# electro3_sensor.net
KiCad netlist of a schematic drawn in Altium Designer
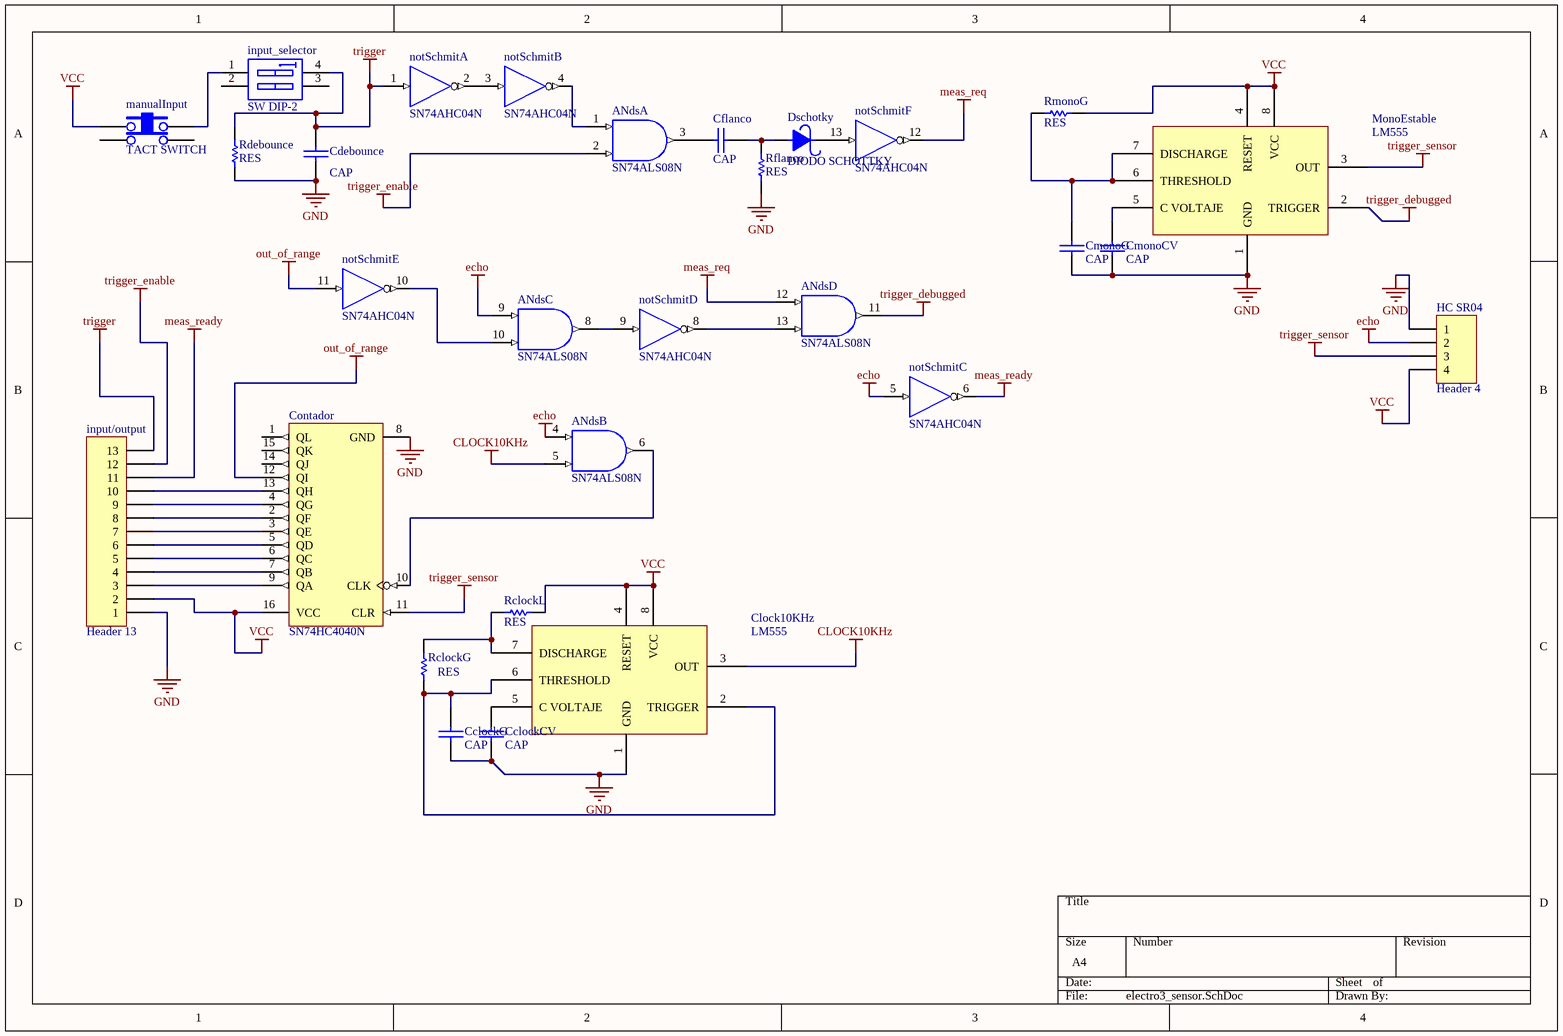
[diagram p0: electro3_sensor.SchDoc]

(export (version "E")
  (design (tool "Eeschema 10.0.6"))
  (components
    (comp (ref "ANds")
      (value "SN74ALS08N")
      (footprint "N014")
      (description "Quadruple 2-Input Positive-AND Gate")
      (fields (field (name "PUBLISHER") "Altium Limited"))
      (libsource (lib "TI Logic Gate 1") (part "SN74ALS08N"))
    )
    (comp (ref "CclockCV") (value "CAP") (footprint "CAP200") (libsource (lib "LIBEBAL") (part "CAP")))
    (comp (ref "CclockG") (value "CAP") (footprint "CAP200") (libsource (lib "LIBEBAL") (part "CAP")))
    (comp (ref "Cdebounce") (value "CAP") (footprint "CAP200") (libsource (lib "LIBEBAL") (part "CAP")))
    (comp (ref "Cflanco") (value "CAP") (footprint "CAP200") (libsource (lib "LIBEBAL") (part "CAP")))
    (comp (ref "Clock10KHz")
      (value "LM555")
      (footprint "DIP8")
      (description "Timer")
      (libsource (lib "LIBEBAL") (part "LM555"))
    )
    (comp (ref "CmonoCV") (value "CAP") (footprint "CAP200") (libsource (lib "LIBEBAL") (part "CAP")))
    (comp (ref "CmonoG") (value "CAP") (footprint "CAP200") (libsource (lib "LIBEBAL") (part "CAP")))
    (comp (ref "Contador")
      (value "SN74HC4040N")
      (footprint "N016")
      (description "12-Bit Asynchronous Binary Counter")
      (fields (field (name "PUBLISHER") "Altium Limited"))
      (libsource (lib "TI Logic Counter") (part "SN74HC4040N"))
    )
    (comp (ref "Dschotky")
      (value "DIODO SCHOTTKY")
      (footprint "DO41")
      (libsource (lib "LIBEBAL") (part "DIODO SCHOTTKY"))
    )
    (comp (ref "HC SR04")
      (value "Header 4")
      (footprint "HDR1X4")
      (description "Header, 4-Pin")
      (fields (field (name "PUBLISHER") "Altium Limited"))
      (libsource (lib "Miscellaneous Connectors") (part "Header 4"))
    )
    (comp (ref "input/output")
      (value "Header 13")
      (footprint "HDR1X13")
      (description "Header, 13-Pin")
      (fields (field (name "PUBLISHER") "Altium Limited"))
      (libsource (lib "Miscellaneous Connectors") (part "Header 13"))
    )
    (comp (ref "input_selector")
      (value "SW DIP-2")
      (footprint "DIP-4")
      (description "DIP Switch, 2 Position, SPST")
      (fields (field (name "PUBLISHER") "Altium Limited"))
      (libsource (lib "Miscellaneous Devices") (part "SW DIP-2"))
    )
    (comp (ref "manualInput")
      (value "TACT SWITCH")
      (footprint "TACTSWITCH")
      (libsource (lib "LIBEBAL") (part "TACT SWITCH"))
    )
    (comp (ref "MonoEstable")
      (value "LM555")
      (footprint "DIP8")
      (description "Timer")
      (libsource (lib "LIBEBAL") (part "LM555"))
    )
    (comp (ref "notSchmit")
      (value "SN74AHC04N")
      (footprint "N014")
      (description "Hex Inverter")
      (fields (field (name "PUBLISHER") "Altium Limited"))
      (libsource (lib "TI Logic Gate 1") (part "SN74AHC04N"))
    )
    (comp (ref "RclockG") (value "RES") (footprint "RES400") (libsource (lib "LIBEBAL") (part "RES")))
    (comp (ref "RclockL") (value "RES") (footprint "RES400") (libsource (lib "LIBEBAL") (part "RES")))
    (comp (ref "Rdebounce") (value "RES") (footprint "RES400") (libsource (lib "LIBEBAL") (part "RES")))
    (comp (ref "Rflanco") (value "RES") (footprint "RES400") (libsource (lib "LIBEBAL") (part "RES")))
    (comp (ref "RmonoG") (value "RES") (footprint "RES400") (libsource (lib "LIBEBAL") (part "RES")))
  )
  (nets
    (net (code "1") (name "CLOCK10KHz") (class "Default")
      (node (ref "ANds") (pin "5") (pinfunction "B_5") (pintype "input"))
      (node (ref "Clock10KHz") (pin "3") (pinfunction "OUT_3") (pintype "passive"))
    )
    (net (code "2") (name "GND") (class "Default")
      (node (ref "ANds") (pin "7") (pinfunction "GND_7") (pintype "power_in"))
      (node (ref "CclockCV") (pin "2") (pinfunction "2_2") (pintype "passive"))
      (node (ref "CclockG") (pin "2") (pinfunction "2_2") (pintype "passive"))
      (node (ref "Cdebounce") (pin "2") (pinfunction "2_2") (pintype "passive"))
      (node (ref "Clock10KHz") (pin "1") (pinfunction "GND_1") (pintype "passive"))
      (node (ref "CmonoCV") (pin "2") (pinfunction "2_2") (pintype "passive"))
      (node (ref "CmonoG") (pin "2") (pinfunction "2_2") (pintype "passive"))
      (node (ref "Contador") (pin "8") (pinfunction "GND_8") (pintype "power_in"))
      (node (ref "HC SR04") (pin "1") (pinfunction "1_1") (pintype "passive"))
      (node (ref "MonoEstable") (pin "1") (pinfunction "GND_1") (pintype "passive"))
      (node (ref "Rdebounce") (pin "1") (pinfunction "1_1") (pintype "passive"))
      (node (ref "Rflanco") (pin "1") (pinfunction "1_1") (pintype "passive"))
      (node (ref "input/output") (pin "1") (pinfunction "1_1") (pintype "passive"))
      (node (ref "notSchmit") (pin "7") (pinfunction "GND_7") (pintype "power_in"))
    )
    (net (code "3") (name "Net-(ANdsA-A)") (class "Default")
      (node (ref "ANds") (pin "1") (pinfunction "A_1") (pintype "input"))
      (node (ref "notSchmit") (pin "4") (pinfunction "Y_4") (pintype "output"))
    )
    (net (code "4") (name "Net-(ANdsA-Y)") (class "Default")
      (node (ref "ANds") (pin "3") (pinfunction "Y_3") (pintype "output"))
      (node (ref "Cflanco") (pin "1") (pinfunction "1_1") (pintype "passive"))
    )
    (net (code "5") (name "Net-(ANdsB-Y)") (class "Default")
      (node (ref "ANds") (pin "6") (pinfunction "Y_6") (pintype "output"))
      (node (ref "Contador") (pin "10") (pinfunction "CLK_10") (pintype "input"))
    )
    (net (code "6") (name "Net-(ANdsC-B)") (class "Default")
      (node (ref "ANds") (pin "10") (pinfunction "B_10") (pintype "input"))
      (node (ref "notSchmit") (pin "10") (pinfunction "Y_10") (pintype "output"))
    )
    (net (code "7") (name "Net-(ANdsC-Y)") (class "Default")
      (node (ref "ANds") (pin "8") (pinfunction "Y_8") (pintype "output"))
      (node (ref "notSchmit") (pin "9") (pinfunction "A_9") (pintype "input"))
    )
    (net (code "8") (name "Net-(ANdsD-B)") (class "Default")
      (node (ref "ANds") (pin "13") (pinfunction "B_13") (pintype "input"))
      (node (ref "notSchmit") (pin "8") (pinfunction "Y_8") (pintype "output"))
    )
    (net (code "9") (name "Net-(Cflanco-Pad2)") (class "Default")
      (node (ref "Cflanco") (pin "2") (pinfunction "2_2") (pintype "passive"))
      (node (ref "Dschotky") (pin "1") (pinfunction "1_1") (pintype "passive"))
      (node (ref "Rflanco") (pin "2") (pinfunction "2_2") (pintype "passive"))
    )
    (net (code "10") (name "Net-(Clock10KHz-C_VOLTAJE)") (class "Default")
      (node (ref "CclockCV") (pin "1") (pinfunction "1_1") (pintype "passive"))
      (node (ref "Clock10KHz") (pin "5") (pinfunction "C_VOLTAJE_5") (pintype "passive"))
    )
    (net (code "11") (name "Net-(Clock10KHz-DISCHARGE)") (class "Default")
      (node (ref "Clock10KHz") (pin "7") (pinfunction "DISCHARGE_7") (pintype "passive"))
      (node (ref "RclockG") (pin "2") (pinfunction "2_2") (pintype "passive"))
      (node (ref "RclockL") (pin "1") (pinfunction "1_1") (pintype "passive"))
    )
    (net (code "12") (name "Net-(Clock10KHz-THRESHOLD)") (class "Default")
      (node (ref "CclockG") (pin "1") (pinfunction "1_1") (pintype "passive"))
      (node (ref "Clock10KHz") (pin "2") (pinfunction "TRIGGER_2") (pintype "passive"))
      (node (ref "Clock10KHz") (pin "6") (pinfunction "THRESHOLD_6") (pintype "passive"))
      (node (ref "RclockG") (pin "1") (pinfunction "1_1") (pintype "passive"))
    )
    (net (code "13") (name "Net-(Contador-QA)") (class "Default")
      (node (ref "Contador") (pin "9") (pinfunction "QA_9") (pintype "output"))
      (node (ref "input/output") (pin "3") (pinfunction "3_3") (pintype "passive"))
    )
    (net (code "14") (name "Net-(Contador-QB)") (class "Default")
      (node (ref "Contador") (pin "7") (pinfunction "QB_7") (pintype "output"))
      (node (ref "input/output") (pin "4") (pinfunction "4_4") (pintype "passive"))
    )
    (net (code "15") (name "Net-(Contador-QC)") (class "Default")
      (node (ref "Contador") (pin "6") (pinfunction "QC_6") (pintype "output"))
      (node (ref "input/output") (pin "5") (pinfunction "5_5") (pintype "passive"))
    )
    (net (code "16") (name "Net-(Contador-QD)") (class "Default")
      (node (ref "Contador") (pin "5") (pinfunction "QD_5") (pintype "output"))
      (node (ref "input/output") (pin "6") (pinfunction "6_6") (pintype "passive"))
    )
    (net (code "17") (name "Net-(Contador-QE)") (class "Default")
      (node (ref "Contador") (pin "3") (pinfunction "QE_3") (pintype "output"))
      (node (ref "input/output") (pin "7") (pinfunction "7_7") (pintype "passive"))
    )
    (net (code "18") (name "Net-(Contador-QF)") (class "Default")
      (node (ref "Contador") (pin "2") (pinfunction "QF_2") (pintype "output"))
      (node (ref "input/output") (pin "8") (pinfunction "8_8") (pintype "passive"))
    )
    (net (code "19") (name "Net-(Contador-QG)") (class "Default")
      (node (ref "Contador") (pin "4") (pinfunction "QG_4") (pintype "output"))
      (node (ref "input/output") (pin "9") (pinfunction "9_9") (pintype "passive"))
    )
    (net (code "20") (name "Net-(Contador-QH)") (class "Default")
      (node (ref "Contador") (pin "13") (pinfunction "QH_13") (pintype "output"))
      (node (ref "input/output") (pin "10") (pinfunction "10_10") (pintype "passive"))
    )
    (net (code "21") (name "Net-(MonoEstable-C_VOLTAJE)") (class "Default")
      (node (ref "CmonoCV") (pin "1") (pinfunction "1_1") (pintype "passive"))
      (node (ref "MonoEstable") (pin "5") (pinfunction "C_VOLTAJE_5") (pintype "passive"))
    )
    (net (code "22") (name "Net-(MonoEstable-DISCHARGE)") (class "Default")
      (node (ref "CmonoG") (pin "1") (pinfunction "1_1") (pintype "passive"))
      (node (ref "MonoEstable") (pin "6") (pinfunction "THRESHOLD_6") (pintype "passive"))
      (node (ref "MonoEstable") (pin "7") (pinfunction "DISCHARGE_7") (pintype "passive"))
      (node (ref "RmonoG") (pin "1") (pinfunction "1_1") (pintype "passive"))
    )
    (net (code "23") (name "Net-(input_selector-A1)") (class "Default")
      (node (ref "input_selector") (pin "1") (pinfunction "A1_1") (pintype "passive"))
      (node (ref "manualInput") (pin "3") (pinfunction "3_3") (pintype "passive"))
    )
    (net (code "24") (name "Net-(notSchmitA-Y)") (class "Default")
      (node (ref "notSchmit") (pin "2") (pinfunction "Y_2") (pintype "output"))
      (node (ref "notSchmit") (pin "3") (pinfunction "A_3") (pintype "input"))
    )
    (net (code "25") (name "Net-(notSchmitF-A)") (class "Default")
      (node (ref "Dschotky") (pin "2") (pinfunction "2_2") (pintype "passive"))
      (node (ref "notSchmit") (pin "13") (pinfunction "A_13") (pintype "input"))
    )
    (net (code "26") (name "VCC") (class "Default")
      (node (ref "ANds") (pin "14") (pinfunction "VCC_14") (pintype "power_in"))
      (node (ref "Clock10KHz") (pin "4") (pinfunction "RESET_4") (pintype "passive"))
      (node (ref "Clock10KHz") (pin "8") (pinfunction "VCC_8") (pintype "passive"))
      (node (ref "Contador") (pin "16") (pinfunction "VCC_16") (pintype "power_in"))
      (node (ref "HC SR04") (pin "4") (pinfunction "4_4") (pintype "passive"))
      (node (ref "MonoEstable") (pin "4") (pinfunction "RESET_4") (pintype "passive"))
      (node (ref "MonoEstable") (pin "8") (pinfunction "VCC_8") (pintype "passive"))
      (node (ref "RclockL") (pin "2") (pinfunction "2_2") (pintype "passive"))
      (node (ref "RmonoG") (pin "2") (pinfunction "2_2") (pintype "passive"))
      (node (ref "input/output") (pin "2") (pinfunction "2_2") (pintype "passive"))
      (node (ref "manualInput") (pin "1") (pinfunction "1_1") (pintype "passive"))
      (node (ref "notSchmit") (pin "14") (pinfunction "VCC_14") (pintype "power_in"))
    )
    (net (code "27") (name "echo") (class "Default")
      (node (ref "ANds") (pin "4") (pinfunction "A_4") (pintype "input"))
      (node (ref "ANds") (pin "9") (pinfunction "A_9") (pintype "input"))
      (node (ref "HC SR04") (pin "2") (pinfunction "2_2") (pintype "passive"))
      (node (ref "notSchmit") (pin "5") (pinfunction "A_5") (pintype "input"))
    )
    (net (code "28") (name "meas_ready") (class "Default")
      (node (ref "input/output") (pin "11") (pinfunction "11_11") (pintype "passive"))
      (node (ref "notSchmit") (pin "6") (pinfunction "Y_6") (pintype "output"))
    )
    (net (code "29") (name "meas_req") (class "Default")
      (node (ref "ANds") (pin "12") (pinfunction "A_12") (pintype "input"))
      (node (ref "notSchmit") (pin "12") (pinfunction "Y_12") (pintype "output"))
    )
    (net (code "30") (name "out_of_range") (class "Default")
      (node (ref "Contador") (pin "12") (pinfunction "QI_12") (pintype "output"))
      (node (ref "notSchmit") (pin "11") (pinfunction "A_11") (pintype "input"))
    )
    (net (code "31") (name "trigger") (class "Default")
      (node (ref "Cdebounce") (pin "1") (pinfunction "1_1") (pintype "passive"))
      (node (ref "Rdebounce") (pin "2") (pinfunction "2_2") (pintype "passive"))
      (node (ref "input/output") (pin "13") (pinfunction "13_13") (pintype "passive"))
      (node (ref "input_selector") (pin "4") (pinfunction "B1_4") (pintype "passive"))
      (node (ref "notSchmit") (pin "1") (pinfunction "A_1") (pintype "input"))
    )
    (net (code "32") (name "trigger_debugged") (class "Default")
      (node (ref "ANds") (pin "11") (pinfunction "Y_11") (pintype "output"))
      (node (ref "MonoEstable") (pin "2") (pinfunction "TRIGGER_2") (pintype "passive"))
    )
    (net (code "33") (name "trigger_enable") (class "Default")
      (node (ref "ANds") (pin "2") (pinfunction "B_2") (pintype "input"))
      (node (ref "input/output") (pin "12") (pinfunction "12_12") (pintype "passive"))
    )
    (net (code "34") (name "trigger_sensor") (class "Default")
      (node (ref "Contador") (pin "11") (pinfunction "CLR_11") (pintype "input"))
      (node (ref "HC SR04") (pin "3") (pinfunction "3_3") (pintype "passive"))
      (node (ref "MonoEstable") (pin "3") (pinfunction "OUT_3") (pintype "passive"))
    )
    (net (code "35") (name "unconnected-(Contador-QJ-Pad14)") (class "Default")
      (node (ref "Contador") (pin "14") (pinfunction "QJ_14") (pintype "output"))
    )
    (net (code "36") (name "unconnected-(Contador-QK-Pad15)") (class "Default")
      (node (ref "Contador") (pin "15") (pinfunction "QK_15") (pintype "output"))
    )
    (net (code "37") (name "unconnected-(Contador-QL-Pad1)") (class "Default")
      (node (ref "Contador") (pin "1") (pinfunction "QL_1") (pintype "output"))
    )
    (net (code "38") (name "unconnected-(input_selector-A2-Pad2)") (class "Default")
      (node (ref "input_selector") (pin "2") (pinfunction "A2_2") (pintype "passive"))
    )
    (net (code "39") (name "unconnected-(input_selector-B2-Pad3)") (class "Default")
      (node (ref "input_selector") (pin "3") (pinfunction "B2_3") (pintype "passive"))
    )
    (net (code "40") (name "unconnected-(manualInput-Pad2)") (class "Default")
      (node (ref "manualInput") (pin "2") (pinfunction "2_2") (pintype "passive"))
    )
    (net (code "41") (name "unconnected-(manualInput-Pad4)") (class "Default")
      (node (ref "manualInput") (pin "4") (pinfunction "4_4") (pintype "passive"))
    )
  )
)
